# Thermal_module.net
KiCad netlist of a schematic drawn in EAGLE
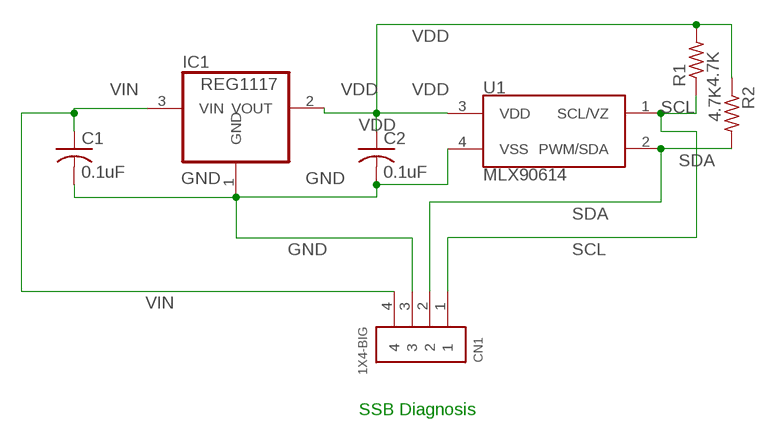
[diagram p0: schematic, sheet 1]

(export (version "E")
  (design (tool "Eeschema 10.0.6"))
  (components
    (comp (ref "C1")
      (value "0.1uF")
      (footprint "eagle-import:C0805")
      (libsource (lib "eagle-import") (part "C-USC0805"))
    )
    (comp (ref "C2")
      (value "0.1uF")
      (footprint "eagle-import:C0805")
      (libsource (lib "eagle-import") (part "C-USC0805"))
    )
    (comp (ref "CN1")
      (value "1X4-BIG")
      (footprint "eagle-import:1X04-BIG")
      (libsource (lib "eagle-import") (part "1X4-BIG"))
    )
    (comp (ref "IC1")
      (value "REG1117")
      (footprint "eagle-import:SOT223")
      (libsource (lib "eagle-import") (part "REG1117"))
    )
    (comp (ref "R1")
      (value "4.7K")
      (footprint "eagle-import:R0805")
      (libsource (lib "eagle-import") (part "R-US_R0805"))
    )
    (comp (ref "R2")
      (value "4.7K")
      (footprint "eagle-import:R0805")
      (libsource (lib "eagle-import") (part "R-US_R0805"))
    )
    (comp (ref "U1")
      (value "MLX90614")
      (footprint "eagle-import:TO-39")
      (libsource (lib "eagle-import") (part "MLX90614"))
    )
  )
  (nets
    (net (code "1") (name "/GND") (class "Default")
      (node (ref "C1") (pin "2") (pinfunction "2_2") (pintype "passive"))
      (node (ref "C2") (pin "2") (pinfunction "2_2") (pintype "passive"))
      (node (ref "CN1") (pin "3") (pinfunction "3_3") (pintype "bidirectional"))
      (node (ref "IC1") (pin "1") (pinfunction "GND_1") (pintype "power_in"))
      (node (ref "U1") (pin "4") (pinfunction "VSS_4") (pintype "bidirectional"))
    )
    (net (code "2") (name "/SCL") (class "Default")
      (node (ref "CN1") (pin "1") (pinfunction "1_1") (pintype "bidirectional"))
      (node (ref "R1") (pin "1") (pinfunction "1_1") (pintype "passive"))
      (node (ref "U1") (pin "1") (pinfunction "SCL/VZ_1") (pintype "bidirectional"))
    )
    (net (code "3") (name "/SDA") (class "Default")
      (node (ref "CN1") (pin "2") (pinfunction "2_2") (pintype "bidirectional"))
      (node (ref "R2") (pin "2") (pinfunction "2_2") (pintype "passive"))
      (node (ref "U1") (pin "2") (pinfunction "PWM/SDA_2") (pintype "bidirectional"))
    )
    (net (code "4") (name "/VDD") (class "Default")
      (node (ref "C2") (pin "1") (pinfunction "1_1") (pintype "passive"))
      (node (ref "IC1") (pin "2") (pinfunction "VOUT_2") (pintype "output"))
      (node (ref "R1") (pin "2") (pinfunction "2_2") (pintype "passive"))
      (node (ref "R2") (pin "1") (pinfunction "1_1") (pintype "passive"))
      (node (ref "U1") (pin "3") (pinfunction "VDD_3") (pintype "bidirectional"))
    )
    (net (code "5") (name "/VIN") (class "Default")
      (node (ref "C1") (pin "1") (pinfunction "1_1") (pintype "passive"))
      (node (ref "CN1") (pin "4") (pinfunction "4_4") (pintype "bidirectional"))
      (node (ref "IC1") (pin "3") (pinfunction "VIN_3") (pintype "input"))
    )
  )
)
